# ToolTron_ToolBoxv2_0.net
KiCad netlist of a schematic drawn in EAGLE
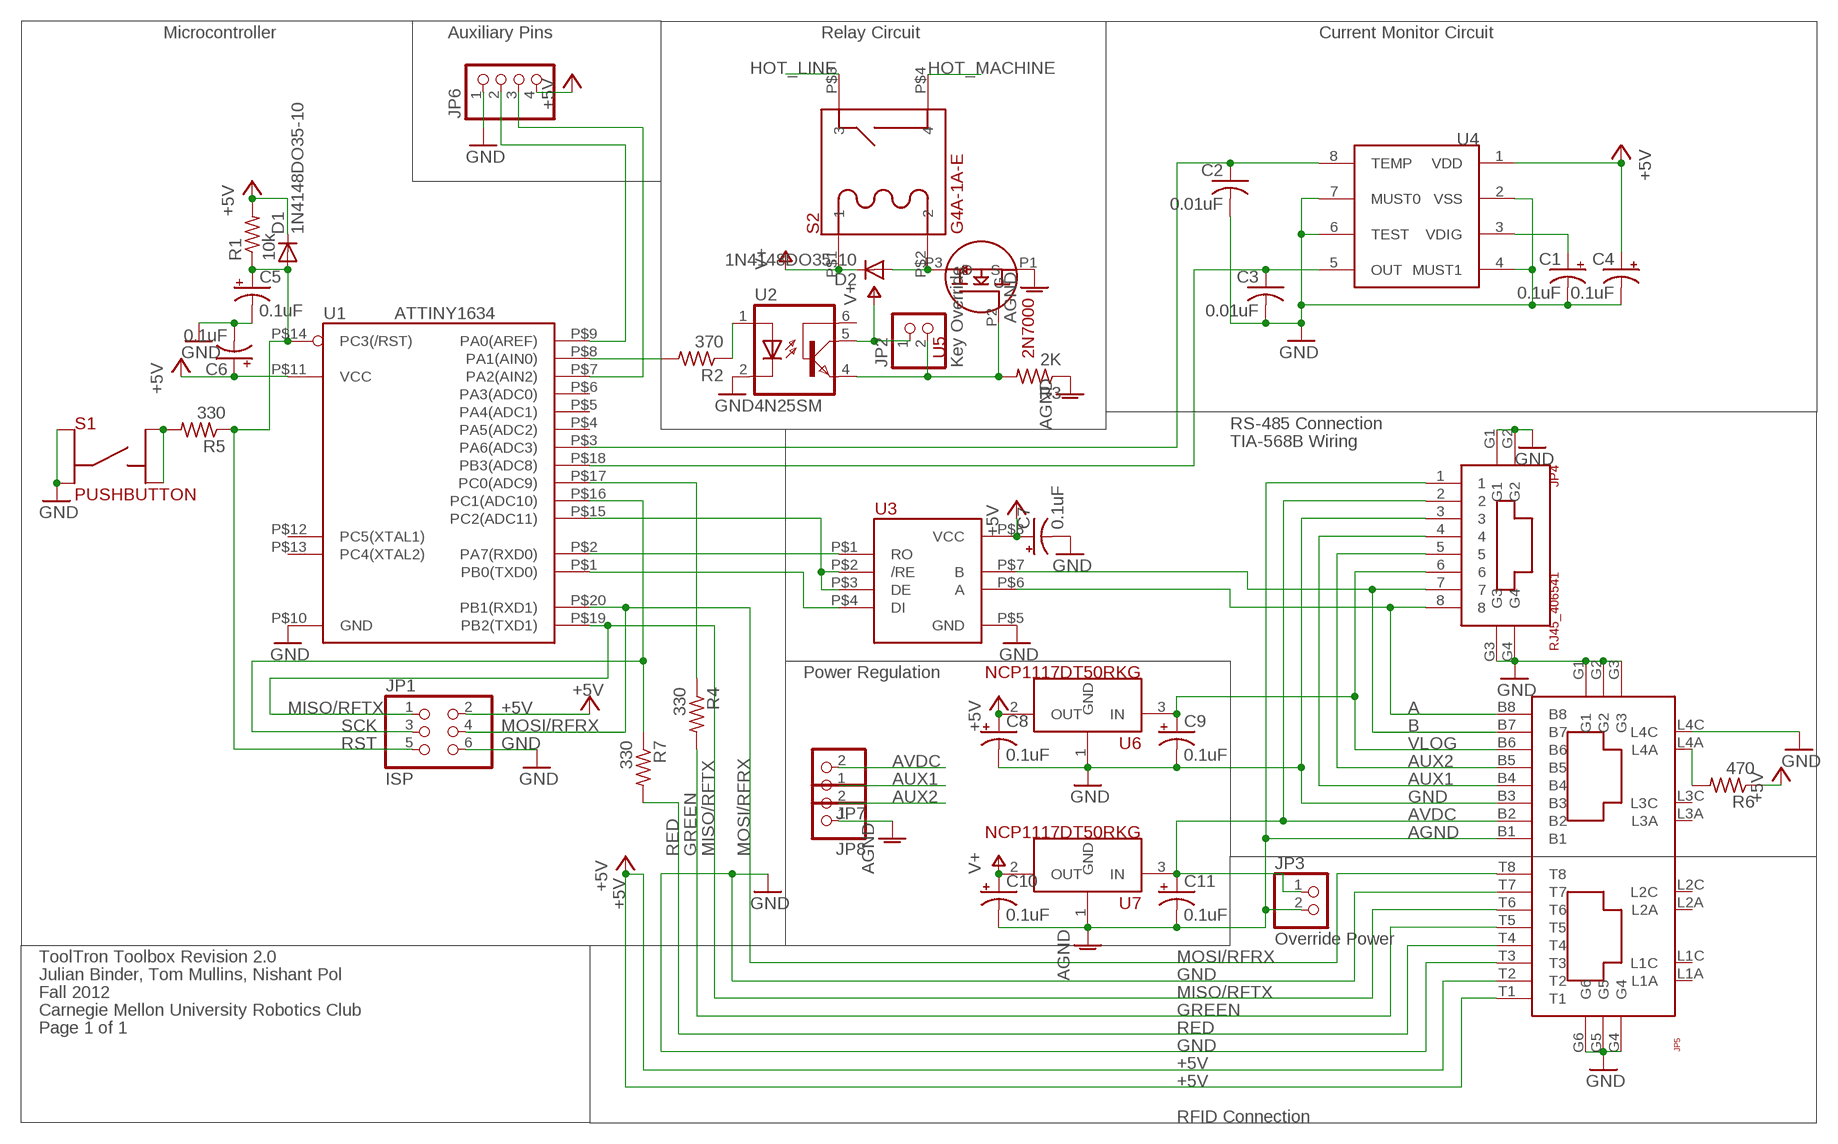
[diagram p0: schematic, sheet 1]

(export (version "E")
  (design (tool "Eeschema 10.0.6"))
  (components
    (comp (ref "C1")
      (value "0.1uF")
      (footprint "eagle-import:UD-4X5,8_NICHICON")
      (libsource (lib "eagle-import") (part "CPOL-USUD-4X5,8"))
    )
    (comp (ref "C2")
      (value "0.01uF")
      (footprint "eagle-import:C0805")
      (libsource (lib "eagle-import") (part "C-USC0805"))
    )
    (comp (ref "C3")
      (value "0.01uF")
      (footprint "eagle-import:C0805")
      (libsource (lib "eagle-import") (part "C-USC0805"))
    )
    (comp (ref "C4")
      (value "0.1uF")
      (footprint "eagle-import:UD-4X5,8_NICHICON")
      (libsource (lib "eagle-import") (part "CPOL-USUD-4X5,8"))
    )
    (comp (ref "C5")
      (value "0.1uF")
      (footprint "eagle-import:E2-5")
      (libsource (lib "eagle-import") (part "CPOL-USE2-5"))
    )
    (comp (ref "C6")
      (value "0.1uF")
      (footprint "eagle-import:E2-5")
      (libsource (lib "eagle-import") (part "CPOL-USE2-5"))
    )
    (comp (ref "C7")
      (value "0.1uF")
      (footprint "eagle-import:E2-5")
      (libsource (lib "eagle-import") (part "CPOL-USE2-5"))
    )
    (comp (ref "C8")
      (value "0.1uF")
      (footprint "eagle-import:E2-5")
      (libsource (lib "eagle-import") (part "CPOL-USE2-5"))
    )
    (comp (ref "C9")
      (value "0.1uF")
      (footprint "eagle-import:E2-5")
      (libsource (lib "eagle-import") (part "CPOL-USE2-5"))
    )
    (comp (ref "C10")
      (value "0.1uF")
      (footprint "eagle-import:UD-4X5,8_NICHICON")
      (libsource (lib "eagle-import") (part "CPOL-USUD-4X5,8"))
    )
    (comp (ref "C11")
      (value "0.1uF")
      (footprint "eagle-import:UD-4X5,8_NICHICON")
      (libsource (lib "eagle-import") (part "CPOL-USUD-4X5,8"))
    )
    (comp (ref "D1")
      (value "1N4148DO35-10")
      (footprint "eagle-import:DO35-10")
      (libsource (lib "eagle-import") (part "1N4148DO35-10"))
    )
    (comp (ref "D2")
      (value "1N4148DO35-10")
      (footprint "eagle-import:DO35-10")
      (libsource (lib "eagle-import") (part "1N4148DO35-10"))
    )
    (comp (ref "JP1")
      (value "ISP")
      (footprint "eagle-import:2X03")
      (libsource (lib "eagle-import") (part "PINHD-2X3"))
    )
    (comp (ref "JP2")
      (value "Key Override")
      (footprint "eagle-import:1X02_OVAL")
      (libsource (lib "eagle-import") (part "HEADER-1X2"))
    )
    (comp (ref "JP3")
      (value "Override Power")
      (footprint "eagle-import:1X02_OVAL")
      (libsource (lib "eagle-import") (part "HEADER-1X2"))
    )
    (comp (ref "JP4")
      (value "RJ45_406541")
      (footprint "eagle-import:1-406541-1")
      (libsource (lib "eagle-import") (part "RJ45_406541"))
    )
    (comp (ref "JP5")
      (value "2XRJ45_RJSAE538X02X")
      (footprint "eagle-import:RJSAE538X02X")
      (libsource (lib "eagle-import") (part "2XRJ45_RJSAE538X02X"))
    )
    (comp (ref "JP6")
      (value "HEADER-1X4ROUND")
      (footprint "eagle-import:1X04_ROUND")
      (libsource (lib "eagle-import") (part "HEADER-1X4ROUND"))
    )
    (comp (ref "JP7")
      (value "HEADER-1X2ROUND")
      (footprint "eagle-import:1X02_ROUND")
      (libsource (lib "eagle-import") (part "HEADER-1X2ROUND"))
    )
    (comp (ref "JP8")
      (value "HEADER-1X2ROUND")
      (footprint "eagle-import:1X02_ROUND")
      (libsource (lib "eagle-import") (part "HEADER-1X2ROUND"))
    )
    (comp (ref "R1")
      (value "10k")
      (footprint "eagle-import:0207_10")
      (libsource (lib "eagle-import") (part "R-US_0207/10"))
    )
    (comp (ref "R2")
      (value "370")
      (footprint "eagle-import:0207_10")
      (libsource (lib "eagle-import") (part "R-US_0207/10"))
    )
    (comp (ref "R3")
      (value "2K")
      (footprint "eagle-import:0207_10")
      (libsource (lib "eagle-import") (part "R-US_0207/10"))
    )
    (comp (ref "R4")
      (value "330")
      (footprint "eagle-import:0207_10")
      (libsource (lib "eagle-import") (part "R-US_0207/10"))
    )
    (comp (ref "R5")
      (value "330")
      (footprint "eagle-import:0207_10")
      (libsource (lib "eagle-import") (part "R-US_0207/10"))
    )
    (comp (ref "R6")
      (value "470")
      (footprint "eagle-import:0207_10")
      (libsource (lib "eagle-import") (part "R-US_0207/10"))
    )
    (comp (ref "R7")
      (value "330")
      (footprint "eagle-import:0207_10")
      (libsource (lib "eagle-import") (part "R-US_0207/10"))
    )
    (comp (ref "S1")
      (value "PUSHBUTTON")
      (footprint "eagle-import:FSM4JH")
      (libsource (lib "eagle-import") (part "PUSHBUTTON"))
    )
    (comp (ref "S2")
      (value "G4A-1A-E")
      (footprint "eagle-import:G4A-1A-E")
      (libsource (lib "eagle-import") (part "G4A-1A-E"))
    )
    (comp (ref "U1")
      (value "ATTINY1634")
      (footprint "eagle-import:SOIC-20")
      (libsource (lib "eagle-import") (part "ATTINY1634"))
    )
    (comp (ref "U2")
      (value "4N25SM")
      (footprint "eagle-import:DIL6-SMD")
      (fields
        (field (name "MF") "FAIRCHILD SEMICONDUCTOR")
        (field (name "MF_1") "FAIRCHILD SEMICONDUCTOR")
        (field (name "MPN") "4N25SM")
        (field (name "OC_FARNELL") "1021152")
        (field (name "OC_NEWARK") "34C2020")
      )
      (libsource (lib "eagle-import") (part "4N?MS25"))
    )
    (comp (ref "U3")
      (value "MAX13082E")
      (footprint "eagle-import:SOIC-8")
      (libsource (lib "eagle-import") (part "MAX13082E"))
    )
    (comp (ref "U4")
      (value "MLX91206")
      (footprint "eagle-import:SOIC-8")
      (libsource (lib "eagle-import") (part "MLX91206"))
    )
    (comp (ref "U5")
      (value "2N7000")
      (footprint "eagle-import:TO-92")
      (libsource (lib "eagle-import") (part "2N7000"))
    )
    (comp (ref "U6")
      (value "NCP1117DT50RKG")
      (footprint "eagle-import:DPAK")
      (libsource (lib "eagle-import") (part "NCP1117DT50RKG"))
    )
    (comp (ref "U7")
      (value "NCP1117DT50RKG")
      (footprint "eagle-import:DPAK")
      (libsource (lib "eagle-import") (part "NCP1117DT50RKG"))
    )
  )
  (nets
    (net (code "1") (name "+5V") (class "Default")
      (node (ref "C4") (pin "+") (pinfunction "+_+") (pintype "passive"))
      (node (ref "C6") (pin "+") (pinfunction "+_+") (pintype "passive"))
      (node (ref "C7") (pin "+") (pinfunction "+_+") (pintype "passive"))
      (node (ref "C8") (pin "+") (pinfunction "+_+") (pintype "passive"))
      (node (ref "D1") (pin "C") (pinfunction "C_C") (pintype "passive"))
      (node (ref "JP1") (pin "2") (pinfunction "2_2") (pintype "passive"))
      (node (ref "JP5") (pin "T1") (pinfunction "T1_T1") (pintype "bidirectional"))
      (node (ref "JP5") (pin "T2") (pinfunction "T2_T2") (pintype "bidirectional"))
      (node (ref "JP6") (pin "4") (pinfunction "4_4") (pintype "passive"))
      (node (ref "R1") (pin "2") (pinfunction "2_2") (pintype "passive"))
      (node (ref "R6") (pin "1") (pinfunction "1_1") (pintype "passive"))
      (node (ref "U1") (pin "P$11") (pinfunction "VCC_P$11") (pintype "power_in"))
      (node (ref "U3") (pin "P$8") (pinfunction "VCC_P$8") (pintype "bidirectional"))
      (node (ref "U4") (pin "1") (pinfunction "VDD_1") (pintype "power_in"))
      (node (ref "U6") (pin "2") (pinfunction "OUT_2") (pintype "bidirectional"))
    )
    (net (code "2") (name "/A") (class "Default")
      (node (ref "JP4") (pin "8") (pinfunction "8_8") (pintype "bidirectional"))
      (node (ref "JP5") (pin "B8") (pinfunction "B8_B8") (pintype "bidirectional"))
      (node (ref "U3") (pin "P$6") (pinfunction "A_P$6") (pintype "bidirectional"))
    )
    (net (code "3") (name "/AUX1") (class "Default")
      (node (ref "JP4") (pin "4") (pinfunction "4_4") (pintype "bidirectional"))
      (node (ref "JP5") (pin "B4") (pinfunction "B4_B4") (pintype "bidirectional"))
      (node (ref "JP7") (pin "1") (pinfunction "1_1") (pintype "passive"))
    )
    (net (code "4") (name "/AUX2") (class "Default")
      (node (ref "JP4") (pin "5") (pinfunction "5_5") (pintype "bidirectional"))
      (node (ref "JP5") (pin "B5") (pinfunction "B5_B5") (pintype "bidirectional"))
      (node (ref "JP8") (pin "2") (pinfunction "2_2") (pintype "passive"))
    )
    (net (code "5") (name "/AVDC") (class "Default")
      (node (ref "C11") (pin "+") (pinfunction "+_+") (pintype "passive"))
      (node (ref "JP3") (pin "1") (pinfunction "1_1") (pintype "passive"))
      (node (ref "JP4") (pin "2") (pinfunction "2_2") (pintype "bidirectional"))
      (node (ref "JP5") (pin "B2") (pinfunction "B2_B2") (pintype "bidirectional"))
      (node (ref "JP7") (pin "2") (pinfunction "2_2") (pintype "passive"))
      (node (ref "U7") (pin "3") (pinfunction "IN_3") (pintype "bidirectional"))
    )
    (net (code "6") (name "/B") (class "Default")
      (node (ref "JP4") (pin "7") (pinfunction "7_7") (pintype "bidirectional"))
      (node (ref "JP5") (pin "B7") (pinfunction "B7_B7") (pintype "bidirectional"))
      (node (ref "U3") (pin "P$7") (pinfunction "B_P$7") (pintype "bidirectional"))
    )
    (net (code "7") (name "/GREEN") (class "Default")
      (node (ref "JP5") (pin "T5") (pinfunction "T5_T5") (pintype "bidirectional"))
      (node (ref "R4") (pin "2") (pinfunction "2_2") (pintype "passive"))
    )
    (net (code "8") (name "/HOT_LINE") (class "Default")
      (node (ref "S2") (pin "P$3") (pinfunction "3_P$3") (pintype "bidirectional"))
    )
    (net (code "9") (name "/HOT_MACHINE") (class "Default")
      (node (ref "S2") (pin "P$4") (pinfunction "4_P$4") (pintype "bidirectional"))
    )
    (net (code "10") (name "/MISO{slash}RFTX") (class "Default")
      (node (ref "JP1") (pin "1") (pinfunction "1_1") (pintype "passive"))
      (node (ref "JP5") (pin "T6") (pinfunction "T6_T6") (pintype "bidirectional"))
      (node (ref "U1") (pin "P$19") (pinfunction "PB2(TXD1)_P$19") (pintype "bidirectional"))
    )
    (net (code "11") (name "/MOSI{slash}RFRX") (class "Default")
      (node (ref "JP1") (pin "4") (pinfunction "4_4") (pintype "passive"))
      (node (ref "JP5") (pin "T8") (pinfunction "T8_T8") (pintype "bidirectional"))
      (node (ref "U1") (pin "P$20") (pinfunction "PB1(RXD1)_P$20") (pintype "bidirectional"))
    )
    (net (code "12") (name "/RED") (class "Default")
      (node (ref "JP5") (pin "T4") (pinfunction "T4_T4") (pintype "bidirectional"))
      (node (ref "R7") (pin "2") (pinfunction "2_2") (pintype "passive"))
    )
    (net (code "13") (name "/RST") (class "Default")
      (node (ref "C5") (pin "+") (pinfunction "+_+") (pintype "passive"))
      (node (ref "D1") (pin "A") (pinfunction "A_A") (pintype "passive"))
      (node (ref "JP1") (pin "5") (pinfunction "5_5") (pintype "passive"))
      (node (ref "R1") (pin "1") (pinfunction "1_1") (pintype "passive"))
      (node (ref "R5") (pin "1") (pinfunction "1_1") (pintype "passive"))
      (node (ref "U1") (pin "P$14") (pinfunction "PC3(/RST)_P$14") (pintype "bidirectional"))
    )
    (net (code "14") (name "/SCK") (class "Default")
      (node (ref "JP1") (pin "3") (pinfunction "3_3") (pintype "passive"))
      (node (ref "R7") (pin "1") (pinfunction "1_1") (pintype "passive"))
      (node (ref "U1") (pin "P$16") (pinfunction "PC1(ADC10)_P$16") (pintype "bidirectional"))
    )
    (net (code "15") (name "/VLOG") (class "Default")
      (node (ref "C9") (pin "+") (pinfunction "+_+") (pintype "passive"))
      (node (ref "JP4") (pin "6") (pinfunction "6_6") (pintype "bidirectional"))
      (node (ref "JP5") (pin "B6") (pinfunction "B6_B6") (pintype "bidirectional"))
      (node (ref "U6") (pin "3") (pinfunction "IN_3") (pintype "bidirectional"))
    )
    (net (code "16") (name "AGND") (class "Default")
      (node (ref "C10") (pin "-") (pinfunction "-_-") (pintype "passive"))
      (node (ref "C11") (pin "-") (pinfunction "-_-") (pintype "passive"))
      (node (ref "JP3") (pin "2") (pinfunction "2_2") (pintype "passive"))
      (node (ref "JP4") (pin "1") (pinfunction "1_1") (pintype "bidirectional"))
      (node (ref "JP5") (pin "B1") (pinfunction "B1_B1") (pintype "bidirectional"))
      (node (ref "JP8") (pin "1") (pinfunction "1_1") (pintype "passive"))
      (node (ref "R3") (pin "1") (pinfunction "1_1") (pintype "passive"))
      (node (ref "U5") (pin "P1") (pinfunction "S_P1") (pintype "bidirectional"))
      (node (ref "U7") (pin "1") (pinfunction "GND_1") (pintype "bidirectional"))
    )
    (net (code "17") (name "GND") (class "Default")
      (node (ref "C1") (pin "-") (pinfunction "-_-") (pintype "passive"))
      (node (ref "C2") (pin "2") (pinfunction "2_2") (pintype "passive"))
      (node (ref "C3") (pin "2") (pinfunction "2_2") (pintype "passive"))
      (node (ref "C4") (pin "-") (pinfunction "-_-") (pintype "passive"))
      (node (ref "C5") (pin "-") (pinfunction "-_-") (pintype "passive"))
      (node (ref "C6") (pin "-") (pinfunction "-_-") (pintype "passive"))
      (node (ref "C7") (pin "-") (pinfunction "-_-") (pintype "passive"))
      (node (ref "C8") (pin "-") (pinfunction "-_-") (pintype "passive"))
      (node (ref "C9") (pin "-") (pinfunction "-_-") (pintype "passive"))
      (node (ref "JP1") (pin "6") (pinfunction "6_6") (pintype "passive"))
      (node (ref "JP4") (pin "3") (pinfunction "3_3") (pintype "bidirectional"))
      (node (ref "JP4") (pin "G1") (pinfunction "G1_G1") (pintype "bidirectional"))
      (node (ref "JP4") (pin "G2") (pinfunction "G2_G2") (pintype "bidirectional"))
      (node (ref "JP4") (pin "G3") (pinfunction "G3_G3") (pintype "bidirectional"))
      (node (ref "JP4") (pin "G4") (pinfunction "G4_G4") (pintype "bidirectional"))
      (node (ref "JP5") (pin "B3") (pinfunction "B3_B3") (pintype "bidirectional"))
      (node (ref "JP5") (pin "G1") (pinfunction "G1_G1") (pintype "bidirectional"))
      (node (ref "JP5") (pin "G2") (pinfunction "G2_G2") (pintype "bidirectional"))
      (node (ref "JP5") (pin "G3") (pinfunction "G3_G3") (pintype "bidirectional"))
      (node (ref "JP5") (pin "G4") (pinfunction "G4_G4") (pintype "bidirectional"))
      (node (ref "JP5") (pin "G5") (pinfunction "G5_G5") (pintype "bidirectional"))
      (node (ref "JP5") (pin "G6") (pinfunction "G6_G6") (pintype "bidirectional"))
      (node (ref "JP5") (pin "L4C") (pinfunction "L4C_L4C") (pintype "bidirectional"))
      (node (ref "JP5") (pin "T3") (pinfunction "T3_T3") (pintype "bidirectional"))
      (node (ref "JP5") (pin "T7") (pinfunction "T7_T7") (pintype "bidirectional"))
      (node (ref "JP6") (pin "1") (pinfunction "1_1") (pintype "passive"))
      (node (ref "S1") (pin "1") (pinfunction "1_1") (pintype "bidirectional"))
      (node (ref "S1") (pin "2") (pinfunction "2_2") (pintype "bidirectional"))
      (node (ref "U1") (pin "P$10") (pinfunction "GND_P$10") (pintype "power_in"))
      (node (ref "U2") (pin "2") (pinfunction "C_2") (pintype "passive"))
      (node (ref "U3") (pin "P$5") (pinfunction "GND_P$5") (pintype "bidirectional"))
      (node (ref "U4") (pin "2") (pinfunction "VSS_2") (pintype "power_in"))
      (node (ref "U4") (pin "4") (pinfunction "MUST1_4") (pintype "bidirectional"))
      (node (ref "U4") (pin "6") (pinfunction "TEST_6") (pintype "bidirectional"))
      (node (ref "U4") (pin "7") (pinfunction "MUST0_7") (pintype "bidirectional"))
      (node (ref "U6") (pin "1") (pinfunction "GND_1") (pintype "bidirectional"))
    )
    (net (code "18") (name "Net-(JP5-PadL4A)") (class "Default")
      (node (ref "JP5") (pin "L4A") (pinfunction "L4A_L4A") (pintype "bidirectional"))
      (node (ref "R6") (pin "2") (pinfunction "2_2") (pintype "passive"))
    )
    (net (code "19") (name "Net-(R5-Pad2)") (class "Default")
      (node (ref "R5") (pin "2") (pinfunction "2_2") (pintype "passive"))
      (node (ref "S1") (pin "3") (pinfunction "3_3") (pintype "bidirectional"))
      (node (ref "S1") (pin "4") (pinfunction "4_4") (pintype "bidirectional"))
    )
    (net (code "20") (name "Net-(S2-2)") (class "Default")
      (node (ref "D2") (pin "A") (pinfunction "A_A") (pintype "passive"))
      (node (ref "S2") (pin "P$2") (pinfunction "2_P$2") (pintype "bidirectional"))
      (node (ref "U5") (pin "P3") (pinfunction "D_P3") (pintype "bidirectional"))
    )
    (net (code "21") (name "Net-(U1-PA0(AREF))") (class "Default")
      (node (ref "JP6") (pin "2") (pinfunction "2_2") (pintype "passive"))
      (node (ref "U1") (pin "P$9") (pinfunction "PA0(AREF)_P$9") (pintype "bidirectional"))
    )
    (net (code "22") (name "Net-(U1-PA1(AIN0))") (class "Default")
      (node (ref "R2") (pin "2") (pinfunction "2_2") (pintype "passive"))
      (node (ref "U1") (pin "P$8") (pinfunction "PA1(AIN0)_P$8") (pintype "bidirectional"))
    )
    (net (code "23") (name "Net-(U1-PA2(AIN2))") (class "Default")
      (node (ref "JP6") (pin "3") (pinfunction "3_3") (pintype "passive"))
      (node (ref "U1") (pin "P$7") (pinfunction "PA2(AIN2)_P$7") (pintype "bidirectional"))
    )
    (net (code "24") (name "Net-(U1-PA6(ADC3))") (class "Default")
      (node (ref "C2") (pin "1") (pinfunction "1_1") (pintype "passive"))
      (node (ref "U1") (pin "P$3") (pinfunction "PA6(ADC3)_P$3") (pintype "bidirectional"))
      (node (ref "U4") (pin "8") (pinfunction "TEMP_8") (pintype "bidirectional"))
    )
    (net (code "25") (name "Net-(U1-PA7(RXD0))") (class "Default")
      (node (ref "U1") (pin "P$2") (pinfunction "PA7(RXD0)_P$2") (pintype "bidirectional"))
      (node (ref "U3") (pin "P$1") (pinfunction "RO_P$1") (pintype "bidirectional"))
    )
    (net (code "26") (name "Net-(U1-PB0(TXD0))") (class "Default")
      (node (ref "U1") (pin "P$1") (pinfunction "PB0(TXD0)_P$1") (pintype "bidirectional"))
      (node (ref "U3") (pin "P$4") (pinfunction "DI_P$4") (pintype "bidirectional"))
    )
    (net (code "27") (name "Net-(U1-PB3(ADC8))") (class "Default")
      (node (ref "C3") (pin "1") (pinfunction "1_1") (pintype "passive"))
      (node (ref "U1") (pin "P$18") (pinfunction "PB3(ADC8)_P$18") (pintype "bidirectional"))
      (node (ref "U4") (pin "5") (pinfunction "OUT_5") (pintype "bidirectional"))
    )
    (net (code "28") (name "Net-(U1-PC0(ADC9))") (class "Default")
      (node (ref "R4") (pin "1") (pinfunction "1_1") (pintype "passive"))
      (node (ref "U1") (pin "P$17") (pinfunction "PC0(ADC9)_P$17") (pintype "bidirectional"))
    )
    (net (code "29") (name "Net-(U1-PC2(ADC11))") (class "Default")
      (node (ref "U1") (pin "P$15") (pinfunction "PC2(ADC11)_P$15") (pintype "bidirectional"))
      (node (ref "U3") (pin "P$2") (pinfunction "/RE_P$2") (pintype "bidirectional"))
      (node (ref "U3") (pin "P$3") (pinfunction "DE_P$3") (pintype "bidirectional"))
    )
    (net (code "30") (name "Net-(U2-A)") (class "Default")
      (node (ref "R2") (pin "1") (pinfunction "1_1") (pintype "passive"))
      (node (ref "U2") (pin "1") (pinfunction "A_1") (pintype "passive"))
    )
    (net (code "31") (name "Net-(U2-EMI)") (class "Default")
      (node (ref "JP2") (pin "2") (pinfunction "2_2") (pintype "passive"))
      (node (ref "R3") (pin "2") (pinfunction "2_2") (pintype "passive"))
      (node (ref "U2") (pin "4") (pinfunction "EMI_4") (pintype "passive"))
      (node (ref "U5") (pin "P2") (pinfunction "G_P2") (pintype "bidirectional"))
    )
    (net (code "32") (name "Net-(U4-VDIG)") (class "Default")
      (node (ref "C1") (pin "+") (pinfunction "+_+") (pintype "passive"))
      (node (ref "U4") (pin "3") (pinfunction "VDIG_3") (pintype "power_in"))
    )
    (net (code "33") (name "V+") (class "Default")
      (node (ref "C10") (pin "+") (pinfunction "+_+") (pintype "passive"))
      (node (ref "D2") (pin "C") (pinfunction "C_C") (pintype "passive"))
      (node (ref "JP2") (pin "1") (pinfunction "1_1") (pintype "passive"))
      (node (ref "S2") (pin "P$1") (pinfunction "1_P$1") (pintype "bidirectional"))
      (node (ref "U2") (pin "5") (pinfunction "COL_5") (pintype "passive"))
      (node (ref "U7") (pin "2") (pinfunction "OUT_2") (pintype "bidirectional"))
    )
    (net (code "34") (name "unconnected-(JP5-PadL1A)") (class "Default")
      (node (ref "JP5") (pin "L1A") (pinfunction "L1A_L1A") (pintype "bidirectional"))
    )
    (net (code "35") (name "unconnected-(JP5-PadL1C)") (class "Default")
      (node (ref "JP5") (pin "L1C") (pinfunction "L1C_L1C") (pintype "bidirectional"))
    )
    (net (code "36") (name "unconnected-(JP5-PadL2A)") (class "Default")
      (node (ref "JP5") (pin "L2A") (pinfunction "L2A_L2A") (pintype "bidirectional"))
    )
    (net (code "37") (name "unconnected-(JP5-PadL2C)") (class "Default")
      (node (ref "JP5") (pin "L2C") (pinfunction "L2C_L2C") (pintype "bidirectional"))
    )
    (net (code "38") (name "unconnected-(JP5-PadL3A)") (class "Default")
      (node (ref "JP5") (pin "L3A") (pinfunction "L3A_L3A") (pintype "bidirectional"))
    )
    (net (code "39") (name "unconnected-(JP5-PadL3C)") (class "Default")
      (node (ref "JP5") (pin "L3C") (pinfunction "L3C_L3C") (pintype "bidirectional"))
    )
    (net (code "40") (name "unconnected-(U1-PA3(ADC0)-PadP$6)") (class "Default")
      (node (ref "U1") (pin "P$6") (pinfunction "PA3(ADC0)_P$6") (pintype "bidirectional"))
    )
    (net (code "41") (name "unconnected-(U1-PA4(ADC1)-PadP$5)") (class "Default")
      (node (ref "U1") (pin "P$5") (pinfunction "PA4(ADC1)_P$5") (pintype "bidirectional"))
    )
    (net (code "42") (name "unconnected-(U1-PA5(ADC2)-PadP$4)") (class "Default")
      (node (ref "U1") (pin "P$4") (pinfunction "PA5(ADC2)_P$4") (pintype "bidirectional"))
    )
    (net (code "43") (name "unconnected-(U1-PC4(XTAL2)-PadP$13)") (class "Default")
      (node (ref "U1") (pin "P$13") (pinfunction "PC4(XTAL2)_P$13") (pintype "bidirectional"))
    )
    (net (code "44") (name "unconnected-(U1-PC5(XTAL1)-PadP$12)") (class "Default")
      (node (ref "U1") (pin "P$12") (pinfunction "PC5(XTAL1)_P$12") (pintype "bidirectional"))
    )
    (net (code "45") (name "unconnected-(U2-BAS-Pad6)") (class "Default")
      (node (ref "U2") (pin "6") (pinfunction "BAS_6") (pintype "passive"))
    )
  )
)
